# IO2.net
KiCad netlist of a schematic drawn in Altium Designer
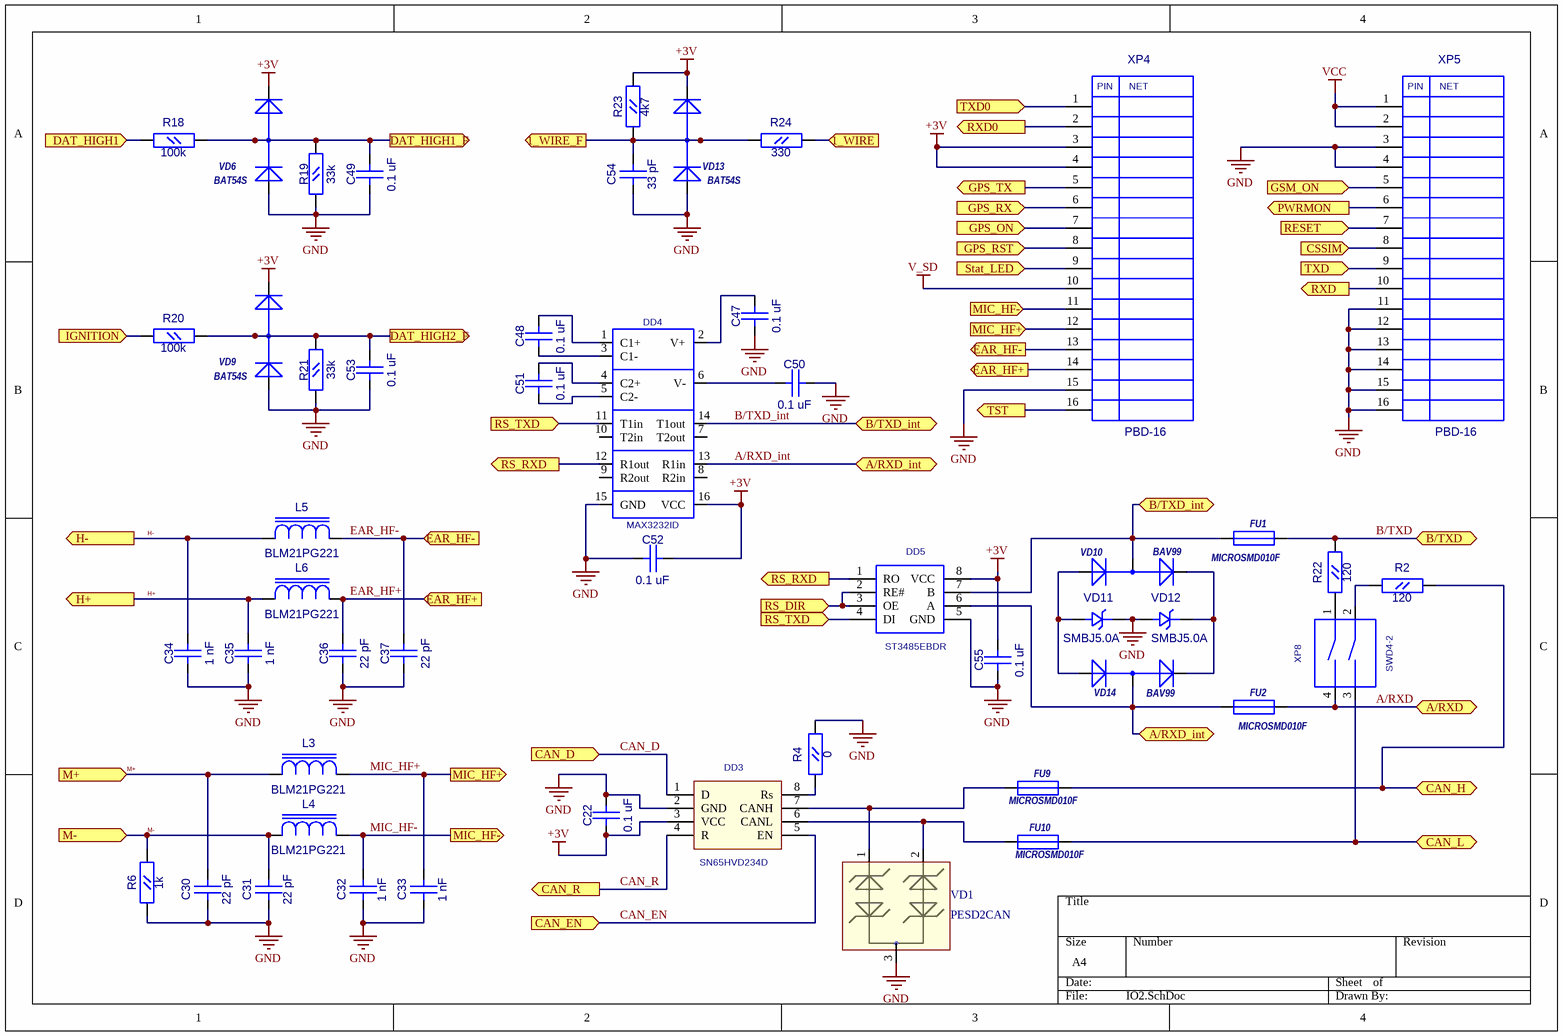
[diagram p0: IO2.SchDoc]

(export (version "E")
  (design (tool "Eeschema 10.0.6"))
  (components
    (comp (ref "C22")
      (value "0.1 uF")
      (footprint "CC0603")
      (description "CC0603")
      (libsource (lib "*") (part "CC0603"))
    )
    (comp (ref "C30")
      (value "22 pF")
      (footprint "CC0603")
      (description "CC0603")
      (libsource (lib "*") (part "CC0603"))
    )
    (comp (ref "C31")
      (value "22 pF")
      (footprint "CC0603")
      (description "CC0603")
      (libsource (lib "*") (part "CC0603"))
    )
    (comp (ref "C32")
      (value "1 nF")
      (footprint "CC0603")
      (description "CC0603")
      (libsource (lib "*") (part "CC0603"))
    )
    (comp (ref "C33")
      (value "1 nF")
      (footprint "CC0603")
      (description "CC0603")
      (libsource (lib "*") (part "CC0603"))
    )
    (comp (ref "C34")
      (value "1 nF")
      (footprint "CC0603")
      (description "CC0603")
      (libsource (lib "*") (part "CC0603"))
    )
    (comp (ref "C35")
      (value "1 nF")
      (footprint "CC0603")
      (description "CC0603")
      (libsource (lib "*") (part "CC0603"))
    )
    (comp (ref "C36")
      (value "22 pF")
      (footprint "CC0603")
      (description "CC0603")
      (libsource (lib "*") (part "CC0603"))
    )
    (comp (ref "C37")
      (value "22 pF")
      (footprint "CC0603")
      (description "CC0603")
      (libsource (lib "*") (part "CC0603"))
    )
    (comp (ref "C47")
      (value "0.1 uF")
      (footprint "CC0603")
      (description "CC0603")
      (libsource (lib "*") (part "CC0603"))
    )
    (comp (ref "C48")
      (value "0.1 uF")
      (footprint "CC0603")
      (description "CC0603")
      (libsource (lib "*") (part "CC0603"))
    )
    (comp (ref "C49")
      (value "0.1 uF")
      (footprint "CC0603")
      (description "CC0603")
      (libsource (lib "*") (part "CC0603"))
    )
    (comp (ref "C50")
      (value "0.1 uF")
      (footprint "CC0603")
      (description "CC0603")
      (libsource (lib "*") (part "CC0603"))
    )
    (comp (ref "C51")
      (value "0.1 uF")
      (footprint "CC0603")
      (description "CC0603")
      (libsource (lib "*") (part "CC0603"))
    )
    (comp (ref "C52")
      (value "0.1 uF")
      (footprint "CC0603")
      (description "CC0603")
      (libsource (lib "*") (part "CC0603"))
    )
    (comp (ref "C53")
      (value "0.1 uF")
      (footprint "CC0603")
      (description "CC0603")
      (libsource (lib "*") (part "CC0603"))
    )
    (comp (ref "C54")
      (value "33 pF")
      (footprint "CC0603")
      (description "CC0603")
      (libsource (lib "*") (part "CC0603"))
    )
    (comp (ref "C55")
      (value "0.1 uF")
      (footprint "CC0603")
      (description "CC0603")
      (libsource (lib "*") (part "CC0603"))
    )
    (comp (ref "DD3")
      (value "SN65HVD234D")
      (footprint "SO-8")
      (description "CAN Transceiver")
      (libsource (lib "gprs_modem") (part "SN65HVD234D"))
    )
    (comp (ref "DD4")
      (value "MAX3232ID")
      (footprint "SO16_M")
      (description "ST232BD/CD")
      (libsource (lib "Schetchik") (part "ST232BD/CD"))
    )
    (comp (ref "DD5")
      (value "ST3485EBDR")
      (footprint "SO-8")
      (description "SP485")
      (libsource (lib "Schetchik") (part "SP485"))
    )
    (comp (ref "FU1")
      (value "MICROSMD010F")
      (footprint "FUSE_1210")
      (description "MICROSMD")
      (libsource (lib "*") (part "MICROSMD"))
    )
    (comp (ref "FU2")
      (value "MICROSMD010F")
      (footprint "FUSE_1210")
      (description "MICROSMD")
      (libsource (lib "*") (part "MICROSMD"))
    )
    (comp (ref "FU9")
      (value "MICROSMD010F")
      (footprint "FUSE_1210")
      (description "MICROSMD")
      (libsource (lib "*") (part "MICROSMD"))
    )
    (comp (ref "FU10")
      (value "MICROSMD010F")
      (footprint "FUSE_1210")
      (description "MICROSMD")
      (libsource (lib "*") (part "MICROSMD"))
    )
    (comp (ref "L3") (value "BLM21PG221") (footprint "RC0805") (libsource (lib "") (part "BLM21PG221_1")))
    (comp (ref "L4") (value "BLM21PG221") (footprint "RC0805") (libsource (lib "") (part "BLM21PG221_1")))
    (comp (ref "L5") (value "BLM21PG221") (footprint "RC0805") (libsource (lib "*") (part "BLM21PG221")))
    (comp (ref "L6") (value "BLM21PG221") (footprint "RC0805") (libsource (lib "*") (part "BLM21PG221")))
    (comp (ref "R2")
      (value "120")
      (footprint "RC0805")
      (description "RC0805")
      (libsource (lib "gprs_modem_2") (part "RC0805"))
    )
    (comp (ref "R4")
      (value "0")
      (footprint "RC0603")
      (description "RC0603")
      (libsource (lib "*") (part "RC0603"))
    )
    (comp (ref "R6")
      (value "1k")
      (footprint "RC0603")
      (description "RC0603")
      (libsource (lib "*") (part "RC0603"))
    )
    (comp (ref "R18")
      (value "100k")
      (footprint "RC0603")
      (description "RC0603")
      (libsource (lib "*") (part "RC0603"))
    )
    (comp (ref "R19")
      (value "33k")
      (footprint "RC0603")
      (description "RC0603")
      (libsource (lib "*") (part "RC0603"))
    )
    (comp (ref "R20")
      (value "100k")
      (footprint "RC0603")
      (description "RC0603")
      (libsource (lib "*") (part "RC0603"))
    )
    (comp (ref "R21")
      (value "33k")
      (footprint "RC0603")
      (description "RC0603")
      (libsource (lib "*") (part "RC0603"))
    )
    (comp (ref "R22")
      (value "120")
      (footprint "RC0805")
      (description "RC0805")
      (libsource (lib "gprs_modem_2") (part "RC0805"))
    )
    (comp (ref "R23")
      (value "4k7")
      (footprint "RC0603")
      (description "RC0603")
      (libsource (lib "*") (part "RC0603"))
    )
    (comp (ref "R24")
      (value "330")
      (footprint "RC0603")
      (description "RC0603")
      (libsource (lib "*") (part "RC0603"))
    )
    (comp (ref "VD1")
      (value "PESD2CAN")
      (footprint "SOT-23(123)")
      (description "TVS for CAN")
      (libsource (lib "gprs_modem") (part "PESD2CAN"))
    )
    (comp (ref "VD6") (value "BAT54S") (footprint "SOT-23(GSD)") (libsource (lib "*") (part "BAT54S")))
    (comp (ref "VD9") (value "BAT54S") (footprint "SOT-23(GSD)") (libsource (lib "*") (part "BAT54S")))
    (comp (ref "VD10")
      (value "BAV99")
      (footprint "SOT-23(GSD)")
      (description "1.0 Ampere General Purpose Rectifier")
      (libsource (lib "gprs_modem") (part "BAV99"))
    )
    (comp (ref "VD11")
      (value "SMBJ5.0A")
      (footprint "SMB")
      (description "SMBJ")
      (libsource (lib "gprs_modem") (part "SMBJ"))
    )
    (comp (ref "VD12")
      (value "SMBJ5.0A")
      (footprint "SMB")
      (description "SMBJ")
      (libsource (lib "gprs_modem") (part "SMBJ"))
    )
    (comp (ref "VD13")
      (value "BAT54S")
      (footprint "SOT-23(GSD)")
      (description "1.0 Ampere General Purpose Rectifier")
      (libsource (lib "gprs_modem") (part "BAT54S"))
    )
    (comp (ref "VD14")
      (value "BAV99")
      (footprint "SOT-23(GSD)")
      (description "1.0 Ampere General Purpose Rectifier")
      (libsource (lib "gprs_modem") (part "BAV99"))
    )
    (comp (ref "XP4") (value "PBD-16") (footprint "PBD16") (libsource (lib "gprs_modem") (part "PBD-16")))
    (comp (ref "XP5") (value "PBD-16") (footprint "PBD16") (libsource (lib "gprs_modem") (part "PBD-16")))
    (comp (ref "XP8") (value "SWD4-2") (footprint "SWD4-2") (libsource (lib "gprs_modem") (part "SWD4-2")))
  )
  (nets
    (net (code "1") (name "+3V") (class "Default")
      (node (ref "C22") (pin "1") (pinfunction "A_1") (pintype "passive"))
      (node (ref "C52") (pin "2") (pinfunction "B_2") (pintype "passive"))
      (node (ref "C55") (pin "2") (pinfunction "B_2") (pintype "passive"))
      (node (ref "DD3") (pin "3") (pinfunction "VCC_3") (pintype "passive"))
      (node (ref "DD4") (pin "16") (pinfunction "VCC_16") (pintype "passive"))
      (node (ref "DD5") (pin "8") (pinfunction "VCC_8") (pintype "passive"))
      (node (ref "R23") (pin "1") (pinfunction "A_1") (pintype "passive"))
      (node (ref "VD13") (pin "2") (pinfunction "K_2") (pintype "passive"))
      (node (ref "VD6") (pin "2") (pinfunction "K_2") (pintype "passive"))
      (node (ref "VD9") (pin "2") (pinfunction "K_2") (pintype "passive"))
      (node (ref "XP4") (pin "3") (pinfunction "3_3") (pintype "passive"))
      (node (ref "XP4") (pin "4") (pinfunction "4_4") (pintype "passive"))
    )
    (net (code "2") (name "/1_WIRE") (class "Default")
      (node (ref "R24") (pin "2") (pinfunction "B_2") (pintype "passive"))
    )
    (net (code "3") (name "/1_WIRE_F") (class "Default")
      (node (ref "C54") (pin "2") (pinfunction "B_2") (pintype "passive"))
      (node (ref "R23") (pin "2") (pinfunction "B_2") (pintype "passive"))
      (node (ref "R24") (pin "1") (pinfunction "A_1") (pintype "passive"))
      (node (ref "VD13") (pin "3") (pinfunction "AK_3") (pintype "passive"))
    )
    (net (code "4") (name "/A{slash}RXD") (class "Default")
      (node (ref "FU2") (pin "1") (pintype "passive"))
      (node (ref "XP8") (pin "4") (pintype "passive"))
    )
    (net (code "5") (name "/A{slash}RXD_int") (class "Default")
      (node (ref "DD4") (pin "13") (pinfunction "R1in_13") (pintype "passive"))
      (node (ref "DD5") (pin "6") (pinfunction "A_6") (pintype "passive"))
      (node (ref "FU2") (pin "2") (pintype "passive"))
      (node (ref "VD14") (pin "3") (pinfunction "AK_3") (pintype "passive"))
    )
    (net (code "6") (name "/B{slash}TXD") (class "Default")
      (node (ref "FU1") (pin "1") (pintype "passive"))
      (node (ref "R22") (pin "2") (pinfunction "B_2") (pintype "passive"))
    )
    (net (code "7") (name "/B{slash}TXD_int") (class "Default")
      (node (ref "DD4") (pin "14") (pinfunction "T1out_14") (pintype "passive"))
      (node (ref "DD5") (pin "7") (pinfunction "B_7") (pintype "passive"))
      (node (ref "FU1") (pin "2") (pintype "passive"))
      (node (ref "VD10") (pin "3") (pinfunction "AK_3") (pintype "passive"))
    )
    (net (code "8") (name "/CAN_D") (class "Default")
      (node (ref "DD3") (pin "1") (pinfunction "D_1") (pintype "passive"))
    )
    (net (code "9") (name "/CAN_EN") (class "Default")
      (node (ref "DD3") (pin "5") (pinfunction "EN_5") (pintype "passive"))
    )
    (net (code "10") (name "/CAN_H") (class "Default")
      (node (ref "FU9") (pin "1") (pintype "passive"))
      (node (ref "R2") (pin "2") (pinfunction "B_2") (pintype "passive"))
    )
    (net (code "11") (name "/CAN_L") (class "Default")
      (node (ref "FU10") (pin "1") (pintype "passive"))
      (node (ref "XP8") (pin "3") (pintype "passive"))
    )
    (net (code "12") (name "/CAN_R") (class "Default")
      (node (ref "DD3") (pin "4") (pinfunction "R_4") (pintype "passive"))
    )
    (net (code "13") (name "/CSSIM") (class "Default")
      (node (ref "XP5") (pin "8") (pinfunction "8_8") (pintype "passive"))
    )
    (net (code "14") (name "/DAT_HIGH1") (class "Default")
      (node (ref "R18") (pin "2") (pinfunction "B_2") (pintype "passive"))
    )
    (net (code "15") (name "/DAT_HIGH1_F") (class "Default")
      (node (ref "C49") (pin "2") (pinfunction "B_2") (pintype "passive"))
      (node (ref "R18") (pin "1") (pinfunction "A_1") (pintype "passive"))
      (node (ref "R19") (pin "1") (pinfunction "A_1") (pintype "passive"))
      (node (ref "VD6") (pin "3") (pinfunction "AK_3") (pintype "passive"))
    )
    (net (code "16") (name "/DAT_HIGH2_F") (class "Default")
      (node (ref "C53") (pin "2") (pinfunction "B_2") (pintype "passive"))
      (node (ref "R20") (pin "1") (pinfunction "A_1") (pintype "passive"))
      (node (ref "R21") (pin "1") (pinfunction "A_1") (pintype "passive"))
      (node (ref "VD9") (pin "3") (pinfunction "AK_3") (pintype "passive"))
    )
    (net (code "17") (name "/EAR_HF+") (class "Default")
      (node (ref "C36") (pin "2") (pinfunction "B_2") (pintype "passive"))
      (node (ref "L6") (pin "1") (pinfunction "A_1") (pintype "passive"))
      (node (ref "XP4") (pin "14") (pinfunction "14_14") (pintype "passive"))
    )
    (net (code "18") (name "/EAR_HF-") (class "Default")
      (node (ref "C37") (pin "2") (pinfunction "B_2") (pintype "passive"))
      (node (ref "L5") (pin "1") (pinfunction "A_1") (pintype "passive"))
      (node (ref "XP4") (pin "13") (pinfunction "13_13") (pintype "passive"))
    )
    (net (code "19") (name "/GPS_ON") (class "Default")
      (node (ref "XP4") (pin "7") (pinfunction "7_7") (pintype "passive"))
    )
    (net (code "20") (name "/GPS_RST") (class "Default")
      (node (ref "XP4") (pin "8") (pinfunction "8_8") (pintype "passive"))
    )
    (net (code "21") (name "/GPS_RX") (class "Default")
      (node (ref "XP4") (pin "6") (pinfunction "6_6") (pintype "passive"))
    )
    (net (code "22") (name "/GPS_TX") (class "Default")
      (node (ref "XP4") (pin "5") (pinfunction "5_5") (pintype "passive"))
    )
    (net (code "23") (name "/GSM_ON") (class "Default")
      (node (ref "XP5") (pin "5") (pinfunction "5_5") (pintype "passive"))
    )
    (net (code "24") (name "/H+") (class "Default")
      (node (ref "C35") (pin "2") (pinfunction "B_2") (pintype "passive"))
      (node (ref "L6") (pin "2") (pinfunction "B_2") (pintype "passive"))
    )
    (net (code "25") (name "/H-") (class "Default")
      (node (ref "C34") (pin "2") (pinfunction "B_2") (pintype "passive"))
      (node (ref "L5") (pin "2") (pinfunction "B_2") (pintype "passive"))
    )
    (net (code "26") (name "/IGNITION") (class "Default")
      (node (ref "R20") (pin "2") (pinfunction "B_2") (pintype "passive"))
    )
    (net (code "27") (name "/M+") (class "Default")
      (node (ref "C30") (pin "2") (pinfunction "B_2") (pintype "passive"))
      (node (ref "L3") (pin "1") (pinfunction "A_1") (pintype "passive"))
    )
    (net (code "28") (name "/M-") (class "Default")
      (node (ref "C31") (pin "2") (pinfunction "B_2") (pintype "passive"))
      (node (ref "L4") (pin "1") (pinfunction "A_1") (pintype "passive"))
      (node (ref "R6") (pin "2") (pinfunction "B_2") (pintype "passive"))
    )
    (net (code "29") (name "/MIC_HF+") (class "Default")
      (node (ref "C33") (pin "2") (pinfunction "B_2") (pintype "passive"))
      (node (ref "L3") (pin "2") (pinfunction "B_2") (pintype "passive"))
      (node (ref "XP4") (pin "12") (pinfunction "12_12") (pintype "passive"))
    )
    (net (code "30") (name "/MIC_HF-") (class "Default")
      (node (ref "C32") (pin "2") (pinfunction "B_2") (pintype "passive"))
      (node (ref "L4") (pin "2") (pinfunction "B_2") (pintype "passive"))
      (node (ref "XP4") (pin "11") (pinfunction "11_11") (pintype "passive"))
    )
    (net (code "31") (name "/PWRMON") (class "Default")
      (node (ref "XP5") (pin "6") (pinfunction "6_6") (pintype "passive"))
    )
    (net (code "32") (name "/RESET") (class "Default")
      (node (ref "XP5") (pin "7") (pinfunction "7_7") (pintype "passive"))
    )
    (net (code "33") (name "/RS_DIR") (class "Default")
      (node (ref "DD5") (pin "2") (pinfunction "RE#_2") (pintype "passive"))
      (node (ref "DD5") (pin "3") (pinfunction "OE_3") (pintype "passive"))
    )
    (net (code "34") (name "/RS_RXD") (class "Default")
      (node (ref "DD4") (pin "12") (pinfunction "R1out_12") (pintype "passive"))
      (node (ref "DD5") (pin "1") (pinfunction "RO_1") (pintype "passive"))
    )
    (net (code "35") (name "/RS_TXD") (class "Default")
      (node (ref "DD4") (pin "11") (pinfunction "T1in_11") (pintype "passive"))
      (node (ref "DD5") (pin "4") (pinfunction "DI_4") (pintype "passive"))
    )
    (net (code "36") (name "/RXD") (class "Default")
      (node (ref "XP5") (pin "10") (pinfunction "10_10") (pintype "passive"))
    )
    (net (code "37") (name "/RXD0") (class "Default")
      (node (ref "XP4") (pin "2") (pinfunction "2_2") (pintype "passive"))
    )
    (net (code "38") (name "/Stat_LED") (class "Default")
      (node (ref "XP4") (pin "9") (pinfunction "9_9") (pintype "passive"))
    )
    (net (code "39") (name "/TST") (class "Default")
      (node (ref "XP4") (pin "16") (pinfunction "16_16") (pintype "passive"))
    )
    (net (code "40") (name "/TXD") (class "Default")
      (node (ref "XP5") (pin "9") (pinfunction "9_9") (pintype "passive"))
    )
    (net (code "41") (name "/TXD0") (class "Default")
      (node (ref "XP4") (pin "1") (pinfunction "1_1") (pintype "passive"))
    )
    (net (code "42") (name "GND") (class "Default")
      (node (ref "C22") (pin "2") (pinfunction "B_2") (pintype "passive"))
      (node (ref "C30") (pin "1") (pinfunction "A_1") (pintype "passive"))
      (node (ref "C31") (pin "1") (pinfunction "A_1") (pintype "passive"))
      (node (ref "C32") (pin "1") (pinfunction "A_1") (pintype "passive"))
      (node (ref "C33") (pin "1") (pinfunction "A_1") (pintype "passive"))
      (node (ref "C34") (pin "1") (pinfunction "A_1") (pintype "passive"))
      (node (ref "C35") (pin "1") (pinfunction "A_1") (pintype "passive"))
      (node (ref "C36") (pin "1") (pinfunction "A_1") (pintype "passive"))
      (node (ref "C37") (pin "1") (pinfunction "A_1") (pintype "passive"))
      (node (ref "C47") (pin "1") (pinfunction "A_1") (pintype "passive"))
      (node (ref "C49") (pin "1") (pinfunction "A_1") (pintype "passive"))
      (node (ref "C50") (pin "1") (pinfunction "A_1") (pintype "passive"))
      (node (ref "C52") (pin "1") (pinfunction "A_1") (pintype "passive"))
      (node (ref "C53") (pin "1") (pinfunction "A_1") (pintype "passive"))
      (node (ref "C54") (pin "1") (pinfunction "A_1") (pintype "passive"))
      (node (ref "C55") (pin "1") (pinfunction "A_1") (pintype "passive"))
      (node (ref "DD3") (pin "2") (pinfunction "GND_2") (pintype "passive"))
      (node (ref "DD4") (pin "15") (pinfunction "GND_15") (pintype "passive"))
      (node (ref "DD5") (pin "5") (pinfunction "GND_5") (pintype "passive"))
      (node (ref "R19") (pin "2") (pinfunction "B_2") (pintype "passive"))
      (node (ref "R21") (pin "2") (pinfunction "B_2") (pintype "passive"))
      (node (ref "R4") (pin "2") (pinfunction "B_2") (pintype "passive"))
      (node (ref "R6") (pin "1") (pinfunction "A_1") (pintype "passive"))
      (node (ref "VD1") (pin "3") (pinfunction "3_3") (pintype "passive"))
      (node (ref "VD11") (pin "2") (pinfunction "K_2") (pintype "passive"))
      (node (ref "VD12") (pin "1") (pinfunction "A_1") (pintype "passive"))
      (node (ref "VD13") (pin "1") (pinfunction "A_1") (pintype "passive"))
      (node (ref "VD6") (pin "1") (pinfunction "A_1") (pintype "passive"))
      (node (ref "VD9") (pin "1") (pinfunction "A_1") (pintype "passive"))
      (node (ref "XP4") (pin "15") (pinfunction "15_15") (pintype "passive"))
      (node (ref "XP5") (pin "11") (pinfunction "11_11") (pintype "passive"))
      (node (ref "XP5") (pin "12") (pinfunction "12_12") (pintype "passive"))
      (node (ref "XP5") (pin "13") (pinfunction "13_13") (pintype "passive"))
      (node (ref "XP5") (pin "14") (pinfunction "14_14") (pintype "passive"))
      (node (ref "XP5") (pin "15") (pinfunction "15_15") (pintype "passive"))
      (node (ref "XP5") (pin "16") (pinfunction "16_16") (pintype "passive"))
      (node (ref "XP5") (pin "3") (pinfunction "3_3") (pintype "passive"))
      (node (ref "XP5") (pin "4") (pinfunction "4_4") (pintype "passive"))
    )
    (net (code "43") (name "Net-(C47-B)") (class "Default")
      (node (ref "C47") (pin "2") (pinfunction "B_2") (pintype "passive"))
      (node (ref "DD4") (pin "2") (pinfunction "V+_2") (pintype "passive"))
    )
    (net (code "44") (name "Net-(C48-A)") (class "Default")
      (node (ref "C48") (pin "1") (pinfunction "A_1") (pintype "passive"))
      (node (ref "DD4") (pin "3") (pinfunction "C1-_3") (pintype "passive"))
    )
    (net (code "45") (name "Net-(C48-B)") (class "Default")
      (node (ref "C48") (pin "2") (pinfunction "B_2") (pintype "passive"))
      (node (ref "DD4") (pin "1") (pinfunction "C1+_1") (pintype "passive"))
    )
    (net (code "46") (name "Net-(C50-B)") (class "Default")
      (node (ref "C50") (pin "2") (pinfunction "B_2") (pintype "passive"))
      (node (ref "DD4") (pin "6") (pinfunction "V-_6") (pintype "passive"))
    )
    (net (code "47") (name "Net-(C51-A)") (class "Default")
      (node (ref "C51") (pin "1") (pinfunction "A_1") (pintype "passive"))
      (node (ref "DD4") (pin "5") (pinfunction "C2-_5") (pintype "passive"))
    )
    (net (code "48") (name "Net-(C51-B)") (class "Default")
      (node (ref "C51") (pin "2") (pinfunction "B_2") (pintype "passive"))
      (node (ref "DD4") (pin "4") (pinfunction "C2+_4") (pintype "passive"))
    )
    (net (code "49") (name "Net-(DD3-CANH)") (class "Default")
      (node (ref "DD3") (pin "7") (pinfunction "CANH_7") (pintype "passive"))
      (node (ref "FU9") (pin "2") (pintype "passive"))
      (node (ref "VD1") (pin "1") (pinfunction "1_1") (pintype "passive"))
    )
    (net (code "50") (name "Net-(DD3-CANL)") (class "Default")
      (node (ref "DD3") (pin "6") (pinfunction "CANL_6") (pintype "passive"))
      (node (ref "FU10") (pin "2") (pintype "passive"))
      (node (ref "VD1") (pin "2") (pinfunction "2_2") (pintype "passive"))
    )
    (net (code "51") (name "Net-(DD3-Rs)") (class "Default")
      (node (ref "DD3") (pin "8") (pinfunction "Rs_8") (pintype "passive"))
      (node (ref "R4") (pin "1") (pinfunction "A_1") (pintype "passive"))
    )
    (net (code "52") (name "Net-(R2-A)") (class "Default")
      (node (ref "R2") (pin "1") (pinfunction "A_1") (pintype "passive"))
      (node (ref "XP8") (pin "2") (pintype "passive"))
    )
    (net (code "53") (name "Net-(R22-A)") (class "Default")
      (node (ref "R22") (pin "1") (pinfunction "A_1") (pintype "passive"))
      (node (ref "XP8") (pin "1") (pintype "passive"))
    )
    (net (code "54") (name "Net-(VD10-A)") (class "Default")
      (node (ref "VD10") (pin "1") (pinfunction "A_1") (pintype "passive"))
      (node (ref "VD11") (pin "1") (pinfunction "A_1") (pintype "passive"))
      (node (ref "VD14") (pin "1") (pinfunction "A_1") (pintype "passive"))
    )
    (net (code "55") (name "Net-(VD10-K)") (class "Default")
      (node (ref "VD10") (pin "2") (pinfunction "K_2") (pintype "passive"))
      (node (ref "VD12") (pin "2") (pinfunction "K_2") (pintype "passive"))
      (node (ref "VD14") (pin "2") (pinfunction "K_2") (pintype "passive"))
    )
    (net (code "56") (name "VCC") (class "Default")
      (node (ref "XP5") (pin "1") (pinfunction "1_1") (pintype "passive"))
      (node (ref "XP5") (pin "2") (pinfunction "2_2") (pintype "passive"))
    )
    (net (code "57") (name "V_SD") (class "Default")
      (node (ref "XP4") (pin "10") (pinfunction "10_10") (pintype "passive"))
    )
    (net (code "58") (name "unconnected-(DD4-R2in-Pad8)") (class "Default")
      (node (ref "DD4") (pin "8") (pinfunction "R2in_8") (pintype "passive"))
    )
    (net (code "59") (name "unconnected-(DD4-R2out-Pad9)") (class "Default")
      (node (ref "DD4") (pin "9") (pinfunction "R2out_9") (pintype "passive"))
    )
    (net (code "60") (name "unconnected-(DD4-T2in-Pad10)") (class "Default")
      (node (ref "DD4") (pin "10") (pinfunction "T2in_10") (pintype "passive"))
    )
    (net (code "61") (name "unconnected-(DD4-T2out-Pad7)") (class "Default")
      (node (ref "DD4") (pin "7") (pinfunction "T2out_7") (pintype "passive"))
    )
  )
)
